# 5V_AC-DC_adi.net
KiCad netlist of a schematic drawn in EAGLE
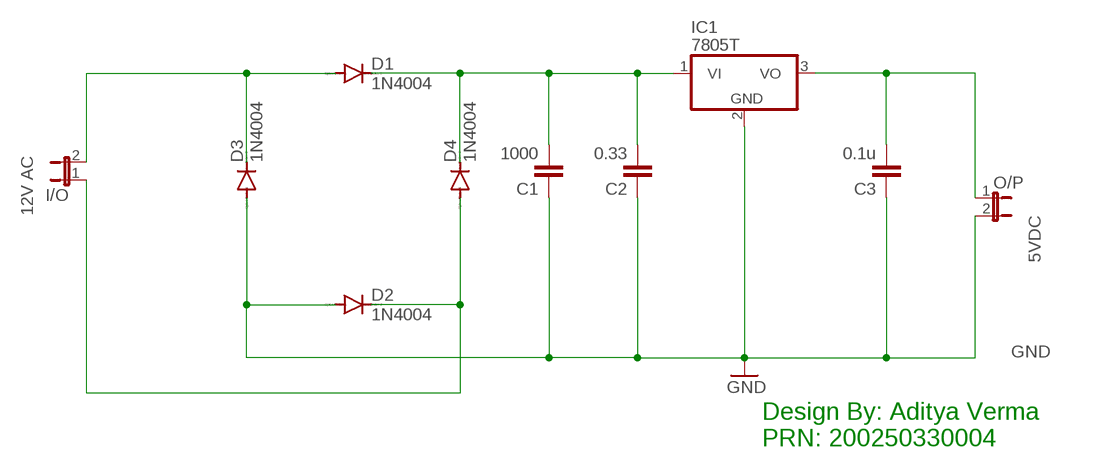
[diagram p0: schematic, sheet 1]

(export (version "E")
  (design (tool "Eeschema 10.0.6"))
  (components
    (comp (ref "C1")
      (value "1000")
      (footprint "eagle-import:C2.5-3")
      (libsource (lib "eagle-import") (part "C2,5-3"))
    )
    (comp (ref "C2")
      (value "0.33")
      (footprint "eagle-import:C2.5-3")
      (libsource (lib "eagle-import") (part "C2,5-3"))
    )
    (comp (ref "C3")
      (value "0.1u")
      (footprint "eagle-import:C2.5-3")
      (libsource (lib "eagle-import") (part "C2,5-3"))
    )
    (comp (ref "D1")
      (value "1N4004")
      (footprint "eagle-import:DO41-10")
      (libsource (lib "eagle-import") (part "1N4004"))
    )
    (comp (ref "D2")
      (value "1N4004")
      (footprint "eagle-import:DO41-10")
      (libsource (lib "eagle-import") (part "1N4004"))
    )
    (comp (ref "D3")
      (value "1N4004")
      (footprint "eagle-import:DO41-10")
      (libsource (lib "eagle-import") (part "1N4004"))
    )
    (comp (ref "D4")
      (value "1N4004")
      (footprint "eagle-import:DO41-10")
      (libsource (lib "eagle-import") (part "1N4004"))
    )
    (comp (ref "I/O")
      (value "JP1E")
      (footprint "eagle-import:JP1")
      (fields (field (name "POPULARITY") "61") (field (name "POPULARITY_1") "12V AC"))
      (libsource (lib "eagle-import") (part "JP1E"))
    )
    (comp (ref "IC1")
      (value "7805T")
      (footprint "eagle-import:TO220H")
      (libsource (lib "eagle-import") (part "78T05"))
    )
    (comp (ref "O/P")
      (value "JP1E")
      (footprint "eagle-import:JP1")
      (fields (field (name "POPULARITY") "61") (field (name "POPULARITY_1") "5VDC"))
      (libsource (lib "eagle-import") (part "JP1E"))
    )
  )
  (nets
    (net (code "1") (name "GND") (class "Default")
      (node (ref "C1") (pin "1") (pinfunction "1_1") (pintype "passive"))
      (node (ref "C2") (pin "1") (pinfunction "1_1") (pintype "passive"))
      (node (ref "C3") (pin "1") (pinfunction "1_1") (pintype "passive"))
      (node (ref "D2") (pin "A") (pinfunction "A_A") (pintype "passive"))
      (node (ref "D3") (pin "A") (pinfunction "A_A") (pintype "passive"))
      (node (ref "IC1") (pin "2") (pinfunction "GND_2") (pintype "passive"))
      (node (ref "O/P") (pin "2") (pinfunction "2_2") (pintype "passive"))
    )
    (net (code "2") (name "Net-(D1-PadA)") (class "Default")
      (node (ref "D1") (pin "A") (pinfunction "A_A") (pintype "passive"))
      (node (ref "D3") (pin "C") (pinfunction "C_C") (pintype "passive"))
      (node (ref "I/O") (pin "2") (pinfunction "2_2") (pintype "passive"))
    )
    (net (code "3") (name "Net-(D2-PadC)") (class "Default")
      (node (ref "D2") (pin "C") (pinfunction "C_C") (pintype "passive"))
      (node (ref "D4") (pin "A") (pinfunction "A_A") (pintype "passive"))
      (node (ref "I/O") (pin "1") (pinfunction "1_1") (pintype "passive"))
    )
    (net (code "4") (name "Net-(IC1-VI)") (class "Default")
      (node (ref "C1") (pin "2") (pinfunction "2_2") (pintype "passive"))
      (node (ref "C2") (pin "2") (pinfunction "2_2") (pintype "passive"))
      (node (ref "D1") (pin "C") (pinfunction "C_C") (pintype "passive"))
      (node (ref "D4") (pin "C") (pinfunction "C_C") (pintype "passive"))
      (node (ref "IC1") (pin "1") (pinfunction "VI_1") (pintype "input"))
    )
    (net (code "5") (name "Net-(IC1-VO)") (class "Default")
      (node (ref "C3") (pin "2") (pinfunction "2_2") (pintype "passive"))
      (node (ref "IC1") (pin "3") (pinfunction "VO_3") (pintype "passive"))
      (node (ref "O/P") (pin "1") (pinfunction "1_1") (pintype "passive"))
    )
  )
)
